# VCLFO_th_2.net
KiCad netlist of a schematic drawn in EAGLE
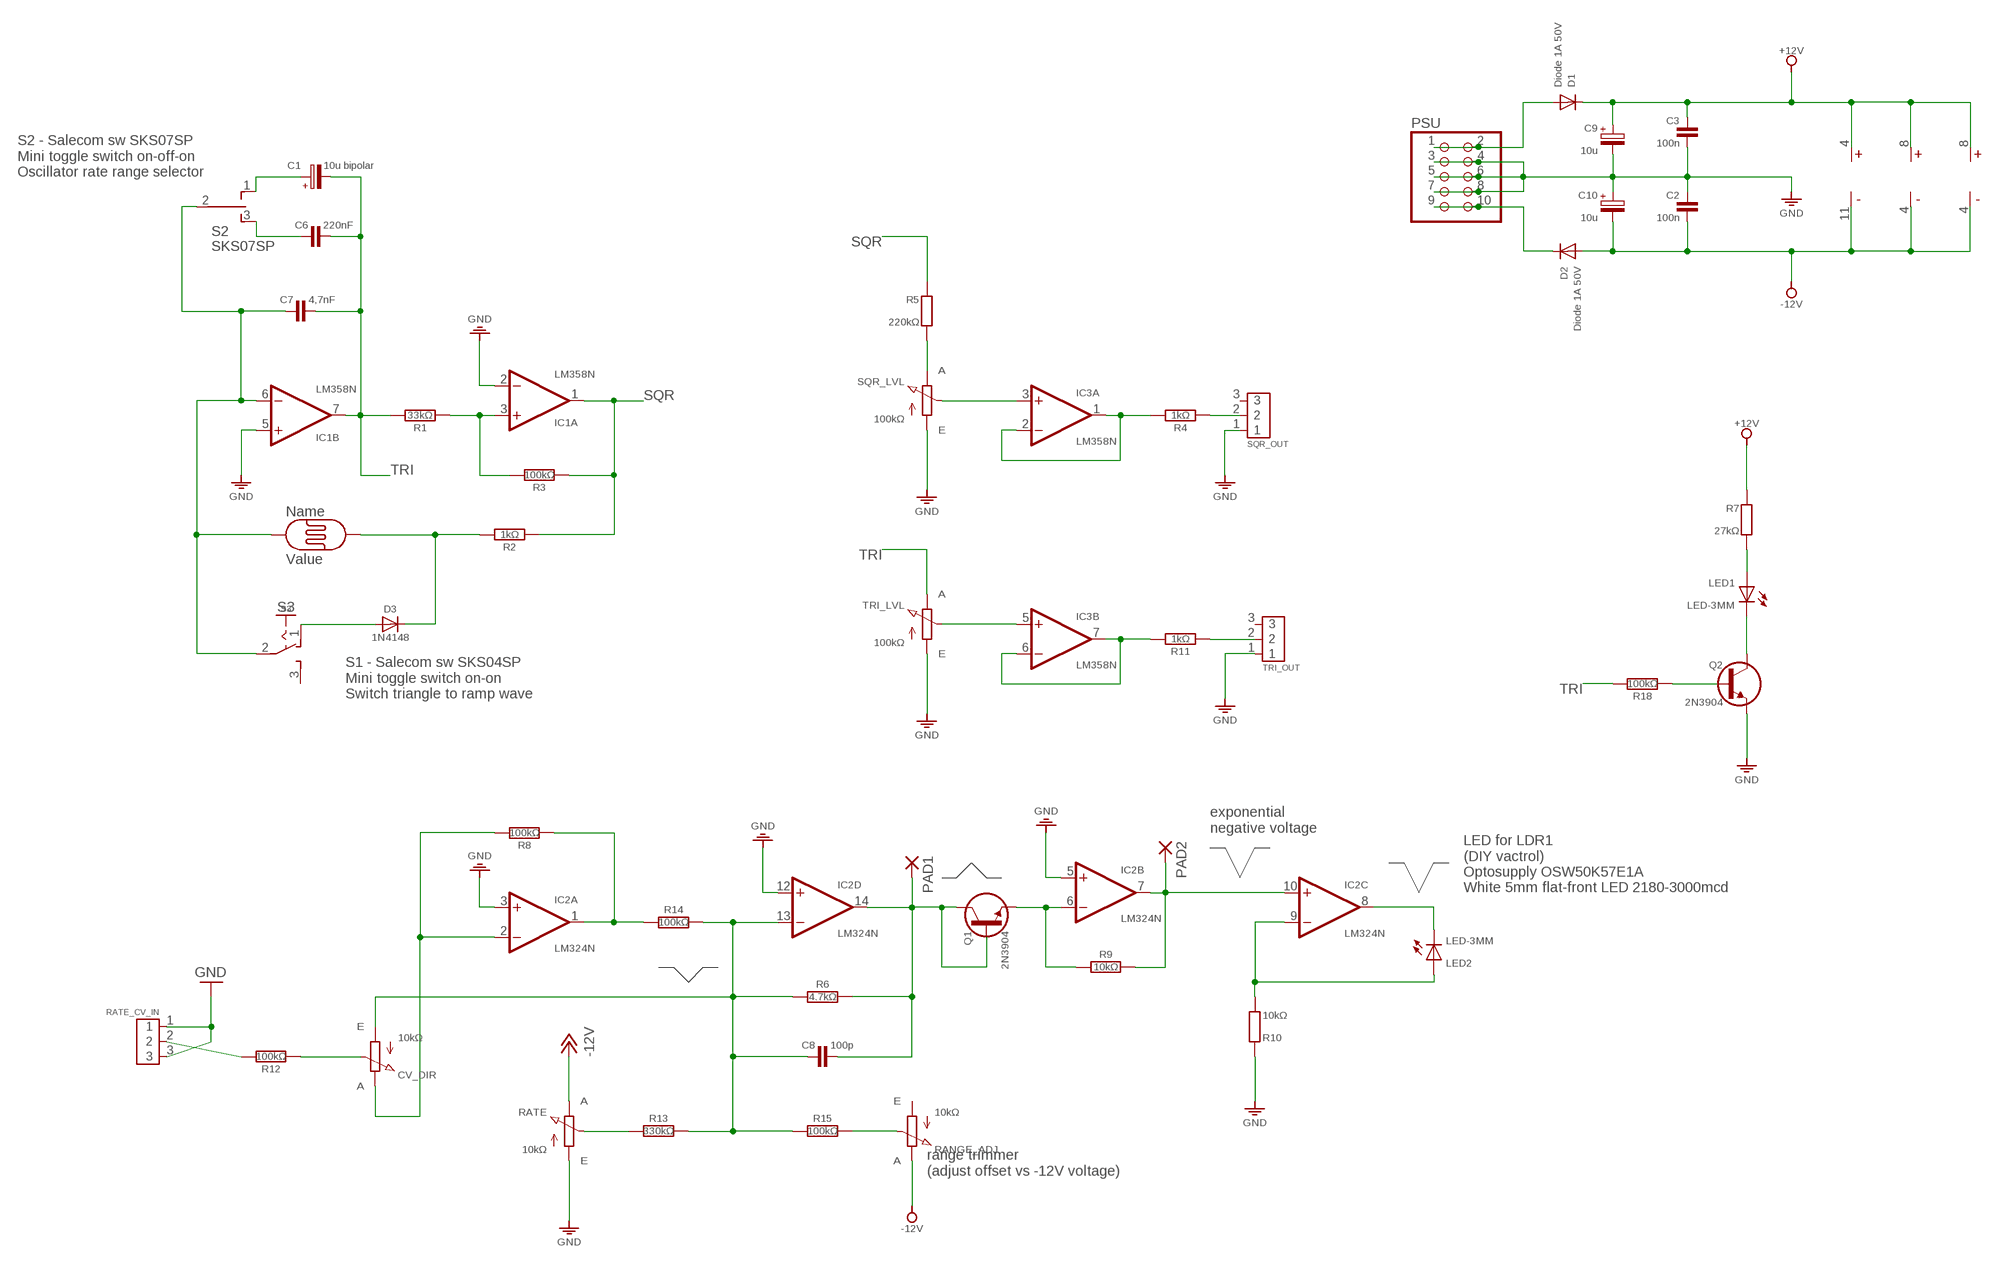
[diagram p0: schematic, sheet 1]

(export (version "E")
  (design (tool "Eeschema 10.0.6"))
  (components
    (comp (ref "C1")
      (value "10u bipolar")
      (footprint "eagle-import:E2,5-4")
      (libsource (lib "eagle-import") (part "CPOLE2,5-4"))
    )
    (comp (ref "C2")
      (value "100n")
      (footprint "eagle-import:C050-020X044_V")
      (libsource (lib "eagle-import") (part "C050-020X044/V"))
    )
    (comp (ref "C3")
      (value "100n")
      (footprint "eagle-import:C050-020X044_V")
      (libsource (lib "eagle-import") (part "C050-020X044/V"))
    )
    (comp (ref "C6")
      (value "220nF")
      (footprint "eagle-import:C050-020X044")
      (libsource (lib "eagle-import") (part "C-H050-020X044"))
    )
    (comp (ref "C7")
      (value "4,7nF")
      (footprint "eagle-import:C075-020X044")
      (libsource (lib "eagle-import") (part "C-H075-020X044"))
    )
    (comp (ref "C8")
      (value "100p")
      (footprint "eagle-import:C025-015X024")
      (libsource (lib "eagle-import") (part "C-H025-015X024"))
    )
    (comp (ref "C9")
      (value "10u")
      (footprint "eagle-import:E2.5-4_V")
      (libsource (lib "eagle-import") (part "CPOLE2,5-4/V"))
    )
    (comp (ref "C10")
      (value "10u")
      (footprint "eagle-import:E2.5-4_V")
      (libsource (lib "eagle-import") (part "CPOLE2,5-4/V"))
    )
    (comp (ref "CV_DIR")
      (value "10kΩ")
      (footprint "eagle-import:CONN-3P")
      (libsource (lib "eagle-import") (part "POT-3P"))
    )
    (comp (ref "D1")
      (value "Diode 1A 50V")
      (footprint "eagle-import:DO35-2_54")
      (libsource (lib "eagle-import") (part "1N4002-2.54"))
    )
    (comp (ref "D2")
      (value "Diode 1A 50V")
      (footprint "eagle-import:DO35-2_54A")
      (libsource (lib "eagle-import") (part "1N4002-2.54A"))
    )
    (comp (ref "D3")
      (value "1N4148")
      (footprint "eagle-import:DO34-10")
      (libsource (lib "eagle-import") (part "DIODE-HDO34-10"))
    )
    (comp (ref "IC1")
      (value "LM358N")
      (footprint "eagle-import:DIL08")
      (libsource (lib "eagle-import") (part "LM358N"))
    )
    (comp (ref "IC2")
      (value "LM324N")
      (footprint "eagle-import:DIL14")
      (libsource (lib "eagle-import") (part "LM324N"))
    )
    (comp (ref "IC3")
      (value "LM358N")
      (footprint "eagle-import:DIL08")
      (libsource (lib "eagle-import") (part "LM358N"))
    )
    (comp (ref "LED1")
      (value "LED-3MM")
      (footprint "eagle-import:LED_3MM")
      (libsource (lib "eagle-import") (part "LED-3MM"))
    )
    (comp (ref "LED2")
      (value "LED-3MM")
      (footprint "eagle-import:LED_3MM")
      (libsource (lib "eagle-import") (part "LED-3MM"))
    )
    (comp (ref "PAD1")
      (value "1,6/0,8")
      (footprint "eagle-import:1,6_0,8")
      (libsource (lib "eagle-import") (part "1,6/0,8"))
    )
    (comp (ref "PAD2")
      (value "1,6/0,8")
      (footprint "eagle-import:1,6_0,8")
      (libsource (lib "eagle-import") (part "1,6/0,8"))
    )
    (comp (ref "PSU")
      (value "PINHD-2X5")
      (footprint "eagle-import:2X05")
      (libsource (lib "eagle-import") (part "PINHD-2X5"))
    )
    (comp (ref "Q1")
      (value "2N3904")
      (footprint "eagle-import:TO92")
      (libsource (lib "eagle-import") (part "2N3904"))
    )
    (comp (ref "Q2")
      (value "2N3904")
      (footprint "eagle-import:TO92")
      (libsource (lib "eagle-import") (part "2N3904"))
    )
    (comp (ref "R1")
      (value "33kΩ")
      (footprint "eagle-import:0204_10")
      (libsource (lib "eagle-import") (part "R-H0204/10"))
    )
    (comp (ref "R2")
      (value "1kΩ")
      (footprint "eagle-import:0204_10")
      (libsource (lib "eagle-import") (part "R-H0204/10"))
    )
    (comp (ref "R3")
      (value "100kΩ")
      (footprint "eagle-import:0204_10")
      (libsource (lib "eagle-import") (part "R-H0204/10"))
    )
    (comp (ref "R4")
      (value "1kΩ")
      (footprint "eagle-import:0204_10")
      (libsource (lib "eagle-import") (part "R-H0204/10"))
    )
    (comp (ref "R5")
      (value "220kΩ")
      (footprint "eagle-import:0204_10-V")
      (libsource (lib "eagle-import") (part "R0204/10-V"))
    )
    (comp (ref "R6")
      (value "4.7kΩ")
      (footprint "eagle-import:0204_10")
      (libsource (lib "eagle-import") (part "R-H0204/10"))
    )
    (comp (ref "R7")
      (value "27kΩ")
      (footprint "eagle-import:0204_10-V")
      (libsource (lib "eagle-import") (part "R0204/10-V"))
    )
    (comp (ref "R8")
      (value "100kΩ")
      (footprint "eagle-import:0204_10")
      (libsource (lib "eagle-import") (part "R-H0204/10"))
    )
    (comp (ref "R9")
      (value "10kΩ")
      (footprint "eagle-import:0204_10")
      (libsource (lib "eagle-import") (part "R-H0204/10"))
    )
    (comp (ref "R10")
      (value "10kΩ")
      (footprint "eagle-import:0204_10")
      (libsource (lib "eagle-import") (part "R0204/10"))
    )
    (comp (ref "R11")
      (value "1kΩ")
      (footprint "eagle-import:0204_10")
      (libsource (lib "eagle-import") (part "R-H0204/10"))
    )
    (comp (ref "R12")
      (value "100kΩ")
      (footprint "eagle-import:0204_10")
      (libsource (lib "eagle-import") (part "R-H0204/10"))
    )
    (comp (ref "R13")
      (value "330kΩ")
      (footprint "eagle-import:0204_10")
      (libsource (lib "eagle-import") (part "R-H0204/10"))
    )
    (comp (ref "R14")
      (value "100kΩ")
      (footprint "eagle-import:0204_10")
      (libsource (lib "eagle-import") (part "R-H0204/10"))
    )
    (comp (ref "R15")
      (value "100kΩ")
      (footprint "eagle-import:0204_10")
      (libsource (lib "eagle-import") (part "R-H0204/10"))
    )
    (comp (ref "R17")
      (value "Token PGM5539")
      (footprint "eagle-import:PHOTOCELL")
      (libsource (lib "eagle-import") (part "PHOTOCELLPTH"))
    )
    (comp (ref "R18")
      (value "100kΩ")
      (footprint "eagle-import:0204_10")
      (libsource (lib "eagle-import") (part "R-H0204/10"))
    )
    (comp (ref "RANGE_ADJ")
      (value "10kΩ")
      (footprint "eagle-import:CONN-3P")
      (libsource (lib "eagle-import") (part "POT-3P"))
    )
    (comp (ref "RATE")
      (value "10kΩ")
      (footprint "eagle-import:CONN-3P")
      (libsource (lib "eagle-import") (part "POT-3P"))
    )
    (comp (ref "RATE_CV_IN")
      (value "CONN-3P-3P")
      (footprint "eagle-import:CONN-3P")
      (libsource (lib "eagle-import") (part "CONN-3P-3P"))
    )
    (comp (ref "S2")
      (value "SKS07SP")
      (footprint "eagle-import:SLSW-1P2T-H")
      (libsource (lib "eagle-import") (part "SL-SW-ON-OFF-ON-H"))
    )
    (comp (ref "S3")
      (value "SKS04SP")
      (footprint "eagle-import:SLSW-1P2T-H")
      (libsource (lib "eagle-import") (part "SL-SW-1P-2T-H"))
    )
    (comp (ref "SQR_LVL")
      (value "100kΩ")
      (footprint "eagle-import:CONN-3P")
      (libsource (lib "eagle-import") (part "POT-3P"))
    )
    (comp (ref "SQR_OUT")
      (value "CONN-3P-3P")
      (footprint "eagle-import:CONN-3P")
      (libsource (lib "eagle-import") (part "CONN-3P-3P"))
    )
    (comp (ref "TRI_LVL")
      (value "100kΩ")
      (footprint "eagle-import:CONN-3P")
      (libsource (lib "eagle-import") (part "POT-3P"))
    )
    (comp (ref "TRI_OUT")
      (value "CONN-3P-3P")
      (footprint "eagle-import:CONN-3P")
      (libsource (lib "eagle-import") (part "CONN-3P-3P"))
    )
  )
  (nets
    (net (code "1") (name "+12V") (class "Default")
      (node (ref "C3") (pin "1") (pinfunction "1_1") (pintype "passive"))
      (node (ref "C9") (pin "+") (pinfunction "+_+") (pintype "passive"))
      (node (ref "D1") (pin "C") (pinfunction "C_C") (pintype "passive"))
      (node (ref "IC1") (pin "8") (pinfunction "V+_8") (pintype "power_in"))
      (node (ref "IC2") (pin "4") (pinfunction "V+_4") (pintype "power_in"))
      (node (ref "IC3") (pin "8") (pinfunction "V+_8") (pintype "power_in"))
      (node (ref "R7") (pin "1") (pinfunction "1_1") (pintype "passive"))
    )
    (net (code "2") (name "-12V") (class "Default")
      (node (ref "C10") (pin "-") (pinfunction "-_-") (pintype "passive"))
      (node (ref "C2") (pin "2") (pinfunction "2_2") (pintype "passive"))
      (node (ref "D2") (pin "A") (pinfunction "A_A") (pintype "passive"))
      (node (ref "IC1") (pin "4") (pinfunction "V-_4") (pintype "power_in"))
      (node (ref "IC2") (pin "11") (pinfunction "V-_11") (pintype "power_in"))
      (node (ref "IC3") (pin "4") (pinfunction "V-_4") (pintype "power_in"))
      (node (ref "RANGE_ADJ") (pin "3") (pinfunction "E_3") (pintype "passive"))
      (node (ref "RATE") (pin "3") (pinfunction "E_3") (pintype "passive"))
    )
    (net (code "3") (name "/SQR") (class "Default")
      (node (ref "IC1") (pin "1") (pinfunction "OUT_1") (pintype "output"))
      (node (ref "R2") (pin "1") (pinfunction "1_1") (pintype "passive"))
      (node (ref "R3") (pin "1") (pinfunction "1_1") (pintype "passive"))
      (node (ref "R5") (pin "1") (pinfunction "1_1") (pintype "passive"))
    )
    (net (code "4") (name "/TRI") (class "Default")
      (node (ref "C1") (pin "-") (pinfunction "-_-") (pintype "passive"))
      (node (ref "C6") (pin "2") (pinfunction "2_2") (pintype "passive"))
      (node (ref "C7") (pin "2") (pinfunction "2_2") (pintype "passive"))
      (node (ref "IC1") (pin "7") (pinfunction "OUT_7") (pintype "output"))
      (node (ref "R1") (pin "2") (pinfunction "2_2") (pintype "passive"))
      (node (ref "R18") (pin "2") (pinfunction "2_2") (pintype "passive"))
      (node (ref "TRI_LVL") (pin "3") (pinfunction "E_3") (pintype "passive"))
    )
    (net (code "5") (name "GND") (class "Default")
      (node (ref "C10") (pin "+") (pinfunction "+_+") (pintype "passive"))
      (node (ref "C2") (pin "1") (pinfunction "1_1") (pintype "passive"))
      (node (ref "C3") (pin "2") (pinfunction "2_2") (pintype "passive"))
      (node (ref "C9") (pin "-") (pinfunction "-_-") (pintype "passive"))
      (node (ref "IC1") (pin "2") (pinfunction "-IN_2") (pintype "input"))
      (node (ref "IC1") (pin "5") (pinfunction "+IN_5") (pintype "input"))
      (node (ref "IC2") (pin "12") (pinfunction "+IN_12") (pintype "input"))
      (node (ref "IC2") (pin "3") (pinfunction "+IN_3") (pintype "input"))
      (node (ref "IC2") (pin "5") (pinfunction "+IN_5") (pintype "input"))
      (node (ref "PSU") (pin "3") (pinfunction "3_3") (pintype "passive"))
      (node (ref "PSU") (pin "4") (pinfunction "4_4") (pintype "passive"))
      (node (ref "PSU") (pin "5") (pinfunction "5_5") (pintype "passive"))
      (node (ref "PSU") (pin "6") (pinfunction "6_6") (pintype "passive"))
      (node (ref "PSU") (pin "7") (pinfunction "7_7") (pintype "passive"))
      (node (ref "PSU") (pin "8") (pinfunction "8_8") (pintype "passive"))
      (node (ref "Q2") (pin "1") (pinfunction "E_1") (pintype "passive"))
      (node (ref "R10") (pin "1") (pinfunction "1_1") (pintype "passive"))
      (node (ref "RATE") (pin "1") (pinfunction "A_1") (pintype "passive"))
      (node (ref "RATE_CV_IN") (pin "1") (pinfunction "1_1") (pintype "bidirectional"))
      (node (ref "RATE_CV_IN") (pin "3") (pinfunction "3_3") (pintype "bidirectional"))
      (node (ref "SQR_LVL") (pin "1") (pinfunction "A_1") (pintype "passive"))
      (node (ref "SQR_OUT") (pin "1") (pinfunction "1_1") (pintype "bidirectional"))
      (node (ref "TRI_LVL") (pin "1") (pinfunction "A_1") (pintype "passive"))
      (node (ref "TRI_OUT") (pin "1") (pinfunction "1_1") (pintype "bidirectional"))
    )
    (net (code "6") (name "Net-(CV_DIR-A)") (class "Default")
      (node (ref "C8") (pin "1") (pinfunction "1_1") (pintype "passive"))
      (node (ref "CV_DIR") (pin "1") (pinfunction "A_1") (pintype "passive"))
      (node (ref "IC2") (pin "13") (pinfunction "-IN_13") (pintype "input"))
      (node (ref "R13") (pin "2") (pinfunction "2_2") (pintype "passive"))
      (node (ref "R14") (pin "2") (pinfunction "2_2") (pintype "passive"))
      (node (ref "R15") (pin "1") (pinfunction "1_1") (pintype "passive"))
      (node (ref "R6") (pin "1") (pinfunction "1_1") (pintype "passive"))
    )
    (net (code "7") (name "Net-(CV_DIR-E)") (class "Default")
      (node (ref "CV_DIR") (pin "3") (pinfunction "E_3") (pintype "passive"))
      (node (ref "IC2") (pin "2") (pinfunction "-IN_2") (pintype "input"))
      (node (ref "R8") (pin "2") (pinfunction "2_2") (pintype "passive"))
    )
    (net (code "8") (name "Net-(CV_DIR-S)") (class "Default")
      (node (ref "CV_DIR") (pin "2") (pinfunction "S_2") (pintype "passive"))
      (node (ref "R12") (pin "1") (pinfunction "1_1") (pintype "passive"))
    )
    (net (code "9") (name "Net-(D1-PadA)") (class "Default")
      (node (ref "D1") (pin "A") (pinfunction "A_A") (pintype "passive"))
      (node (ref "PSU") (pin "1") (pinfunction "1_1") (pintype "passive"))
      (node (ref "PSU") (pin "2") (pinfunction "2_2") (pintype "passive"))
    )
    (net (code "10") (name "Net-(D2-PadC)") (class "Default")
      (node (ref "D2") (pin "C") (pinfunction "C_C") (pintype "passive"))
      (node (ref "PSU") (pin "10") (pinfunction "10_10") (pintype "passive"))
      (node (ref "PSU") (pin "9") (pinfunction "9_9") (pintype "passive"))
    )
    (net (code "11") (name "Net-(IC1A-+IN)") (class "Default")
      (node (ref "IC1") (pin "3") (pinfunction "+IN_3") (pintype "input"))
      (node (ref "R1") (pin "1") (pinfunction "1_1") (pintype "passive"))
      (node (ref "R3") (pin "2") (pinfunction "2_2") (pintype "passive"))
    )
    (net (code "12") (name "Net-(IC1B--IN)") (class "Default")
      (node (ref "C7") (pin "1") (pinfunction "1_1") (pintype "passive"))
      (node (ref "IC1") (pin "6") (pinfunction "-IN_6") (pintype "input"))
      (node (ref "R17") (pin "1") (pinfunction "P$1_1") (pintype "bidirectional"))
      (node (ref "S2") (pin "2") (pinfunction "P_2") (pintype "passive"))
      (node (ref "S3") (pin "2") (pinfunction "P_2") (pintype "passive"))
    )
    (net (code "13") (name "Net-(IC2A-OUT)") (class "Default")
      (node (ref "IC2") (pin "1") (pinfunction "OUT_1") (pintype "output"))
      (node (ref "R14") (pin "1") (pinfunction "1_1") (pintype "passive"))
      (node (ref "R8") (pin "1") (pinfunction "1_1") (pintype "passive"))
    )
    (net (code "14") (name "Net-(IC2B--IN)") (class "Default")
      (node (ref "IC2") (pin "6") (pinfunction "-IN_6") (pintype "input"))
      (node (ref "Q1") (pin "1") (pinfunction "E_1") (pintype "passive"))
      (node (ref "R9") (pin "1") (pinfunction "1_1") (pintype "passive"))
    )
    (net (code "15") (name "Net-(IC2B-OUT)") (class "Default")
      (node (ref "IC2") (pin "10") (pinfunction "+IN_10") (pintype "input"))
      (node (ref "IC2") (pin "7") (pinfunction "OUT_7") (pintype "output"))
      (node (ref "PAD2") (pin "1") (pinfunction "P_1") (pintype "passive"))
      (node (ref "R9") (pin "2") (pinfunction "2_2") (pintype "passive"))
    )
    (net (code "16") (name "Net-(IC2C--IN)") (class "Default")
      (node (ref "IC2") (pin "9") (pinfunction "-IN_9") (pintype "input"))
      (node (ref "LED2") (pin "A") (pinfunction "A_A") (pintype "passive"))
      (node (ref "R10") (pin "2") (pinfunction "2_2") (pintype "passive"))
    )
    (net (code "17") (name "Net-(IC2C-OUT)") (class "Default")
      (node (ref "IC2") (pin "8") (pinfunction "OUT_8") (pintype "output"))
      (node (ref "LED2") (pin "K") (pinfunction "C_K") (pintype "passive"))
    )
    (net (code "18") (name "Net-(IC2D-OUT)") (class "Default")
      (node (ref "C8") (pin "2") (pinfunction "2_2") (pintype "passive"))
      (node (ref "IC2") (pin "14") (pinfunction "OUT_14") (pintype "output"))
      (node (ref "PAD1") (pin "1") (pinfunction "P_1") (pintype "passive"))
      (node (ref "Q1") (pin "2") (pinfunction "B_2") (pintype "passive"))
      (node (ref "Q1") (pin "3") (pinfunction "C_3") (pintype "passive"))
      (node (ref "R6") (pin "2") (pinfunction "2_2") (pintype "passive"))
    )
    (net (code "19") (name "Net-(IC3A-+IN)") (class "Default")
      (node (ref "IC3") (pin "3") (pinfunction "+IN_3") (pintype "input"))
      (node (ref "SQR_LVL") (pin "2") (pinfunction "S_2") (pintype "passive"))
    )
    (net (code "20") (name "Net-(IC3A--IN)") (class "Default")
      (node (ref "IC3") (pin "1") (pinfunction "OUT_1") (pintype "output"))
      (node (ref "IC3") (pin "2") (pinfunction "-IN_2") (pintype "input"))
      (node (ref "R4") (pin "2") (pinfunction "2_2") (pintype "passive"))
    )
    (net (code "21") (name "Net-(IC3B-+IN)") (class "Default")
      (node (ref "IC3") (pin "5") (pinfunction "+IN_5") (pintype "input"))
      (node (ref "TRI_LVL") (pin "2") (pinfunction "S_2") (pintype "passive"))
    )
    (net (code "22") (name "Net-(IC3B--IN)") (class "Default")
      (node (ref "IC3") (pin "6") (pinfunction "-IN_6") (pintype "input"))
      (node (ref "IC3") (pin "7") (pinfunction "OUT_7") (pintype "output"))
      (node (ref "R11") (pin "2") (pinfunction "2_2") (pintype "passive"))
    )
    (net (code "23") (name "Net-(LED1-C)") (class "Default")
      (node (ref "LED1") (pin "K") (pinfunction "C_K") (pintype "passive"))
      (node (ref "Q2") (pin "3") (pinfunction "C_3") (pintype "passive"))
    )
    (net (code "24") (name "Net-(LED1-PadA)") (class "Default")
      (node (ref "LED1") (pin "A") (pinfunction "A_A") (pintype "passive"))
      (node (ref "R7") (pin "2") (pinfunction "2_2") (pintype "passive"))
    )
    (net (code "25") (name "Net-(Q2-B)") (class "Default")
      (node (ref "Q2") (pin "2") (pinfunction "B_2") (pintype "passive"))
      (node (ref "R18") (pin "1") (pinfunction "1_1") (pintype "passive"))
    )
    (net (code "26") (name "Net-(R4-Pad1)") (class "Default")
      (node (ref "R4") (pin "1") (pinfunction "1_1") (pintype "passive"))
      (node (ref "SQR_OUT") (pin "2") (pinfunction "2_2") (pintype "bidirectional"))
    )
    (net (code "27") (name "Net-(R11-Pad1)") (class "Default")
      (node (ref "R11") (pin "1") (pinfunction "1_1") (pintype "passive"))
      (node (ref "TRI_OUT") (pin "2") (pinfunction "2_2") (pintype "bidirectional"))
    )
    (net (code "28") (name "Net-(R12-Pad2)") (class "Default")
      (node (ref "R12") (pin "2") (pinfunction "2_2") (pintype "passive"))
      (node (ref "RATE_CV_IN") (pin "2") (pinfunction "2_2") (pintype "bidirectional"))
    )
    (net (code "29") (name "Net-(R17-P$2)") (class "Default")
      (node (ref "D3") (pin "C") (pinfunction "C_C") (pintype "passive"))
      (node (ref "R17") (pin "2") (pinfunction "P$2_2") (pintype "bidirectional"))
      (node (ref "R2") (pin "2") (pinfunction "2_2") (pintype "passive"))
    )
    (net (code "30") (name "Net-(RANGE_ADJ-S)") (class "Default")
      (node (ref "R15") (pin "2") (pinfunction "2_2") (pintype "passive"))
      (node (ref "RANGE_ADJ") (pin "2") (pinfunction "S_2") (pintype "passive"))
    )
    (net (code "31") (name "Net-(RATE-S)") (class "Default")
      (node (ref "R13") (pin "1") (pinfunction "1_1") (pintype "passive"))
      (node (ref "RATE") (pin "2") (pinfunction "S_2") (pintype "passive"))
    )
    (net (code "32") (name "Net-(S2-O)") (class "Default")
      (node (ref "C1") (pin "+") (pinfunction "+_+") (pintype "passive"))
      (node (ref "S2") (pin "1") (pinfunction "O_1") (pintype "passive"))
    )
    (net (code "33") (name "Net-(S2-S)") (class "Default")
      (node (ref "C6") (pin "1") (pinfunction "1_1") (pintype "passive"))
      (node (ref "S2") (pin "3") (pinfunction "S_3") (pintype "passive"))
    )
    (net (code "34") (name "Net-(S3-O)") (class "Default")
      (node (ref "D3") (pin "A") (pinfunction "A_A") (pintype "passive"))
      (node (ref "S3") (pin "1") (pinfunction "O_1") (pintype "passive"))
    )
    (net (code "35") (name "Net-(SQR_LVL-E)") (class "Default")
      (node (ref "R5") (pin "2") (pinfunction "2_2") (pintype "passive"))
      (node (ref "SQR_LVL") (pin "3") (pinfunction "E_3") (pintype "passive"))
    )
    (net (code "36") (name "unconnected-(RANGE_ADJ-A-Pad1)") (class "Default")
      (node (ref "RANGE_ADJ") (pin "1") (pinfunction "A_1") (pintype "passive"))
    )
    (net (code "37") (name "unconnected-(S3-S-Pad3)") (class "Default")
      (node (ref "S3") (pin "3") (pinfunction "S_3") (pintype "passive"))
    )
    (net (code "38") (name "unconnected-(SQR_OUT-Pad3)") (class "Default")
      (node (ref "SQR_OUT") (pin "3") (pinfunction "3_3") (pintype "bidirectional"))
    )
    (net (code "39") (name "unconnected-(TRI_OUT-Pad3)") (class "Default")
      (node (ref "TRI_OUT") (pin "3") (pinfunction "3_3") (pintype "bidirectional"))
    )
  )
)
